# AT91.net
KiCad netlist of a schematic drawn in Altium Designer
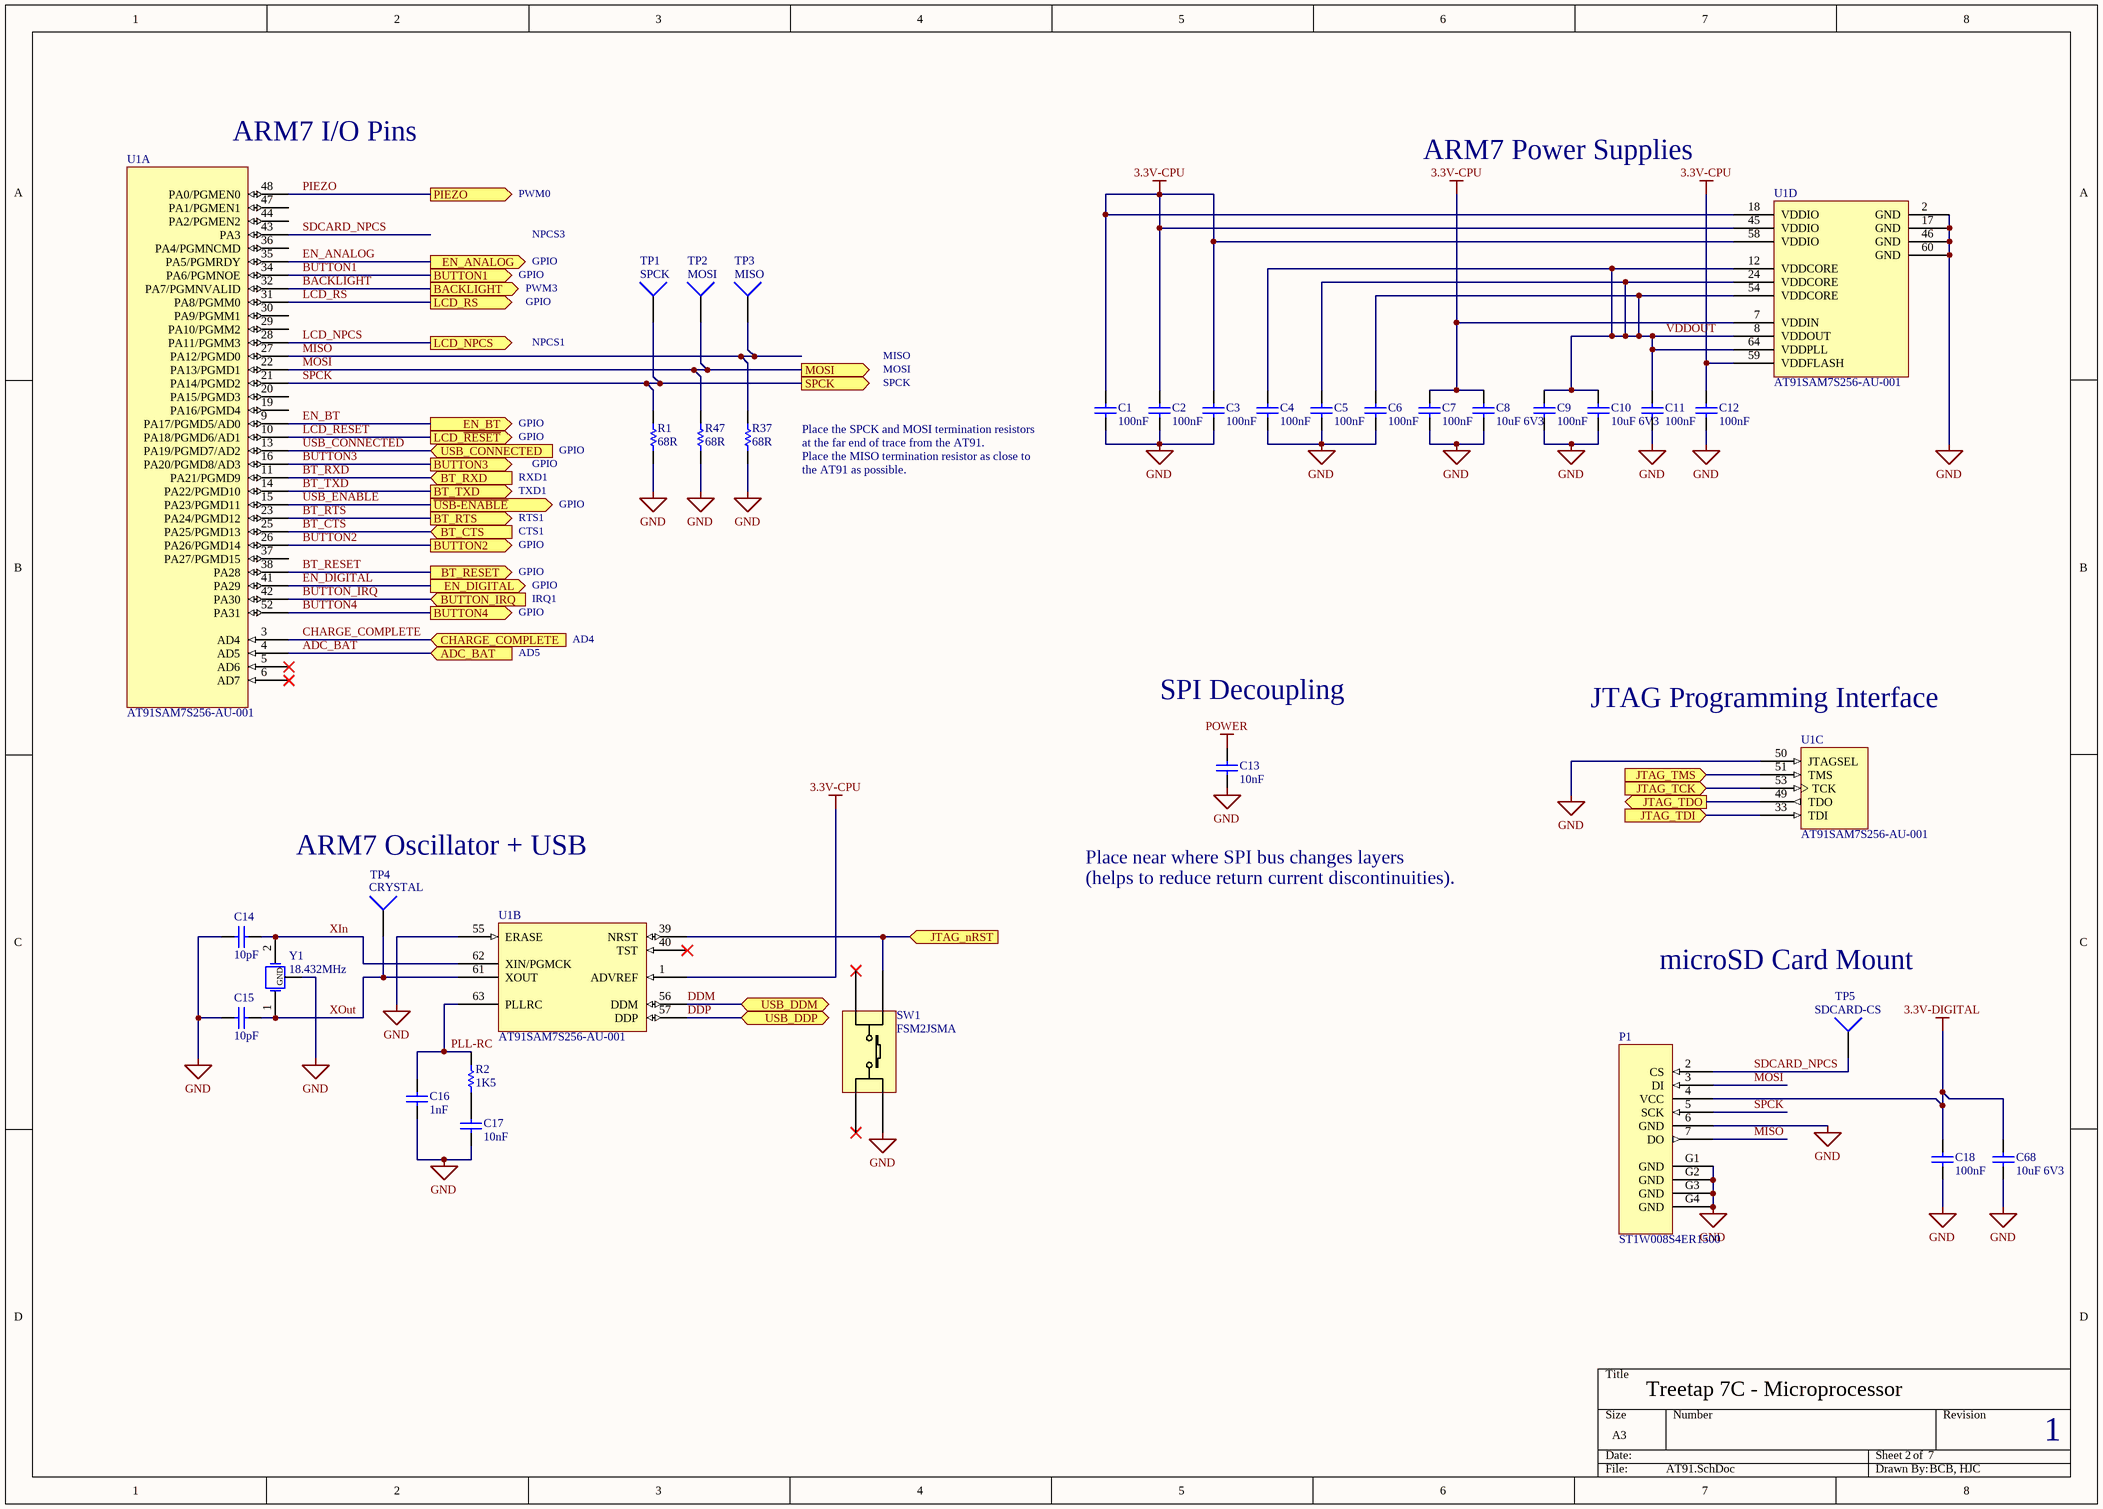
[diagram p0: AT91.SchDoc]

(export (version "E")
  (design (tool "Eeschema 10.0.6"))
  (components
    (comp (ref "C1")
      (value "100nF")
      (footprint "CC0603")
      (description "0603 Capacitor")
      (fields (field (name "PART NUMBER") "100nF_CC0603"))
      (libsource (lib "ECE_Component_Library_2") (part "100nF_CC0603"))
    )
    (comp (ref "C2")
      (value "100nF")
      (footprint "CC0603")
      (description "0603 Capacitor")
      (fields (field (name "PART NUMBER") "100nF_CC0603"))
      (libsource (lib "ECE_Component_Library_2") (part "100nF_CC0603"))
    )
    (comp (ref "C3")
      (value "100nF")
      (footprint "CC0603")
      (description "0603 Capacitor")
      (fields (field (name "PART NUMBER") "100nF_CC0603"))
      (libsource (lib "ECE_Component_Library_2") (part "100nF_CC0603"))
    )
    (comp (ref "C4")
      (value "100nF")
      (footprint "CC0603")
      (description "0603 Capacitor")
      (fields (field (name "PART NUMBER") "100nF_CC0603"))
      (libsource (lib "ECE_Component_Library_2") (part "100nF_CC0603"))
    )
    (comp (ref "C5")
      (value "100nF")
      (footprint "CC0603")
      (description "0603 Capacitor")
      (fields (field (name "PART NUMBER") "100nF_CC0603"))
      (libsource (lib "ECE_Component_Library_2") (part "100nF_CC0603"))
    )
    (comp (ref "C6")
      (value "100nF")
      (footprint "CC0603")
      (description "0603 Capacitor")
      (fields (field (name "PART NUMBER") "100nF_CC0603"))
      (libsource (lib "ECE_Component_Library_2") (part "100nF_CC0603"))
    )
    (comp (ref "C7")
      (value "100nF")
      (footprint "CC0603")
      (description "0603 Capacitor")
      (fields (field (name "PART NUMBER") "100nF_CC0603"))
      (libsource (lib "ECE_Component_Library_2") (part "100nF_CC0603"))
    )
    (comp (ref "C8")
      (value "10uF 6V3")
      (footprint "CC0603")
      (description "10uF 6.3V 0603 ceramic capacitor")
      (fields (field (name "MANUFACTURER") "Multicomp") (field (name "PART NUMBER") "MCCA000517"))
      (libsource (lib "TreetapParts") (part "10uF_CC0603_6V3"))
    )
    (comp (ref "C9")
      (value "100nF")
      (footprint "CC0603")
      (description "0603 Capacitor")
      (fields (field (name "PART NUMBER") "100nF_CC0603"))
      (libsource (lib "ECE_Component_Library_2") (part "100nF_CC0603"))
    )
    (comp (ref "C10")
      (value "10uF 6V3")
      (footprint "CC0603")
      (description "10uF 6.3V 0603 ceramic capacitor")
      (fields (field (name "MANUFACTURER") "Multicomp") (field (name "PART NUMBER") "MCCA000517"))
      (libsource (lib "TreetapParts") (part "10uF_CC0603_6V3"))
    )
    (comp (ref "C11")
      (value "100nF")
      (footprint "CC0603")
      (description "0603 Capacitor")
      (fields (field (name "PART NUMBER") "100nF_CC0603"))
      (libsource (lib "ECE_Component_Library_2") (part "100nF_CC0603"))
    )
    (comp (ref "C12")
      (value "100nF")
      (footprint "CC0603")
      (description "0603 Capacitor")
      (fields (field (name "PART NUMBER") "100nF_CC0603"))
      (libsource (lib "ECE_Component_Library_2") (part "100nF_CC0603"))
    )
    (comp (ref "C13")
      (value "10nF")
      (footprint "CC0603")
      (description "0603 Capacitor")
      (fields (field (name "PART NUMBER") "10nF_CC0603"))
      (libsource (lib "ECE_Component_Library_2") (part "10nF_CC0603"))
    )
    (comp (ref "C14")
      (value "10pF")
      (footprint "CC0603")
      (description "0603 Capacitor")
      (fields (field (name "PART NUMBER") "10pF_CC0603"))
      (libsource (lib "ECE_Component_Library_2") (part "10pF_CC0603"))
    )
    (comp (ref "C15")
      (value "10pF")
      (footprint "CC0603")
      (description "0603 Capacitor")
      (fields (field (name "PART NUMBER") "10pF_CC0603"))
      (libsource (lib "ECE_Component_Library_2") (part "10pF_CC0603"))
    )
    (comp (ref "C16")
      (value "1nF")
      (footprint "CC0603")
      (description "0603 Capacitor")
      (fields (field (name "PART NUMBER") "1nF_CC0603"))
      (libsource (lib "ECE_Component_Library_2") (part "1nF_CC0603"))
    )
    (comp (ref "C17")
      (value "10nF")
      (footprint "CC0603")
      (description "0603 Capacitor")
      (fields (field (name "PART NUMBER") "10nF_CC0603"))
      (libsource (lib "ECE_Component_Library_2") (part "10nF_CC0603"))
    )
    (comp (ref "C18")
      (value "100nF")
      (footprint "CC0603")
      (description "0603 Capacitor")
      (fields (field (name "PART NUMBER") "100nF_CC0603"))
      (libsource (lib "ECE_Component_Library_2") (part "100nF_CC0603"))
    )
    (comp (ref "C68")
      (value "10uF 6V3")
      (footprint "CC0603")
      (description "10uF 6.3V 0603 ceramic capacitor")
      (fields (field (name "MANUFACTURER") "Multicomp") (field (name "PART NUMBER") "MCCA000517"))
      (libsource (lib "TreetapParts") (part "10uF_CC0603_6V3"))
    )
    (comp (ref "P1")
      (value "ST1W008S4ER1500")
      (footprint "ST1W008S4ER1500")
      (description "microSD mount")
      (fields (field (name "MANUFACTURER") "JAE"))
      (libsource (lib "TreetapParts") (part "ST1W008S4ER1500"))
    )
    (comp (ref "R1")
      (value "68R")
      (footprint "R0603")
      (description "0603 Resistor")
      (fields (field (name "PART NUMBER") "68R_R0603"))
      (libsource (lib "ECE_Component_Library_2") (part "68R_R0603"))
    )
    (comp (ref "R2")
      (value "1K5")
      (footprint "R0603")
      (description "0603 Resistor")
      (fields (field (name "PART NUMBER") "1K5_R0603"))
      (libsource (lib "ECE_Component_Library_2") (part "1K5_R0603"))
    )
    (comp (ref "R37")
      (value "68R")
      (footprint "R0603")
      (description "0603 Resistor")
      (fields (field (name "PART NUMBER") "68R_R0603"))
      (libsource (lib "ECE_Component_Library_2") (part "68R_R0603"))
    )
    (comp (ref "R47")
      (value "68R")
      (footprint "R0603")
      (description "0603 Resistor")
      (fields (field (name "PART NUMBER") "68R_R0603"))
      (libsource (lib "ECE_Component_Library_2") (part "68R_R0603"))
    )
    (comp (ref "SW1")
      (value "FSM2JSMA")
      (footprint "FSM2JSMA")
      (description "DPST SMD Switch")
      (fields (field (name "MANUFACTURER") "Tyco Electronics"))
      (libsource (lib "TreetapParts") (part "FSM2JSMA"))
    )
    (comp (ref "TP1")
      (value "SPCK")
      (footprint "SMTP_1")
      (description "Test point hook (surface mount)")
      (fields (field (name "MANUFACTURER") "Harwin") (field (name "PART NUMBER") "S1751-46"))
      (libsource (lib "TreetapParts") (part "SMTestPoint"))
    )
    (comp (ref "TP2")
      (value "MOSI")
      (footprint "SMTP_1")
      (description "Test point hook (surface mount)")
      (fields (field (name "MANUFACTURER") "Harwin") (field (name "PART NUMBER") "S1751-46"))
      (libsource (lib "TreetapParts") (part "SMTestPoint"))
    )
    (comp (ref "TP3")
      (value "MISO")
      (footprint "SMTP_1")
      (description "Test point hook (surface mount)")
      (fields (field (name "MANUFACTURER") "Harwin") (field (name "PART NUMBER") "S1751-46"))
      (libsource (lib "TreetapParts") (part "SMTestPoint"))
    )
    (comp (ref "TP4")
      (value "CRYSTAL")
      (footprint "SMTP_1")
      (description "Test point hook (surface mount)")
      (fields (field (name "MANUFACTURER") "Harwin") (field (name "PART NUMBER") "S1751-46"))
      (libsource (lib "TreetapParts") (part "SMTestPoint"))
    )
    (comp (ref "TP5")
      (value "SDCARD-CS")
      (footprint "SMTP_1")
      (description "Test point hook (surface mount)")
      (fields (field (name "MANUFACTURER") "Harwin") (field (name "PART NUMBER") "S1751-46"))
      (libsource (lib "TreetapParts") (part "SMTestPoint"))
    )
    (comp (ref "U1")
      (value "AT91SAM7S256-AU-001")
      (footprint "LQFP64_L")
      (fields (field (name "MANUFACTURER") "Atmel") (field (name "PART NUMBER") "AT91SAM7S256"))
      (libsource (lib "") (part "AT91SAM7S256-AU-001_1"))
    )
    (comp (ref "Y1")
      (value "18.432MHz")
      (footprint "ABM10-18.432MHZ-E20-T")
      (description "18.432MHz SMT crystal 2x2.5mm 20ppm")
      (fields
        (field (name "PART NUMBER") "ABM10-18.432MHZ-E20-T")
        (field (name "MANUFACTURER") "Abracon Corporation")
      )
      (libsource (lib "TreetapParts") (part "ABM10-18.432MHZ-E20-T"))
    )
  )
  (nets
    (net (code "1") (name "/ADC_BAT") (class "Default")
      (node (ref "U1") (pin "4") (pinfunction "AD5_4") (pintype "input"))
    )
    (net (code "2") (name "/BACKLIGHT") (class "Default")
      (node (ref "U1") (pin "32") (pinfunction "PA7/PGMNVALID_32") (pintype "bidirectional"))
    )
    (net (code "3") (name "/BT_CTS") (class "Default")
      (node (ref "U1") (pin "25") (pinfunction "PA25/PGMD13_25") (pintype "bidirectional"))
    )
    (net (code "4") (name "/BT_RESET") (class "Default")
      (node (ref "U1") (pin "38") (pinfunction "PA28_38") (pintype "bidirectional"))
    )
    (net (code "5") (name "/BT_RTS") (class "Default")
      (node (ref "U1") (pin "23") (pinfunction "PA24/PGMD12_23") (pintype "bidirectional"))
    )
    (net (code "6") (name "/BT_RXD") (class "Default")
      (node (ref "U1") (pin "11") (pinfunction "PA21/PGMD9_11") (pintype "bidirectional"))
    )
    (net (code "7") (name "/BT_TXD") (class "Default")
      (node (ref "U1") (pin "14") (pinfunction "PA22/PGMD10_14") (pintype "bidirectional"))
    )
    (net (code "8") (name "/BUTTON1") (class "Default")
      (node (ref "U1") (pin "34") (pinfunction "PA6/PGMNOE_34") (pintype "bidirectional"))
    )
    (net (code "9") (name "/BUTTON2") (class "Default")
      (node (ref "U1") (pin "26") (pinfunction "PA26/PGMD14_26") (pintype "bidirectional"))
    )
    (net (code "10") (name "/BUTTON3") (class "Default")
      (node (ref "U1") (pin "16") (pinfunction "PA20/PGMD8/AD3_16") (pintype "bidirectional"))
    )
    (net (code "11") (name "/BUTTON4") (class "Default")
      (node (ref "U1") (pin "52") (pinfunction "PA31_52") (pintype "bidirectional"))
    )
    (net (code "12") (name "/BUTTON_IRQ") (class "Default")
      (node (ref "U1") (pin "42") (pinfunction "PA30_42") (pintype "bidirectional"))
    )
    (net (code "13") (name "/CHARGE_COMPLETE") (class "Default")
      (node (ref "U1") (pin "3") (pinfunction "AD4_3") (pintype "input"))
    )
    (net (code "14") (name "/DDM") (class "Default")
      (node (ref "U1") (pin "56") (pinfunction "DDM_56") (pintype "bidirectional"))
    )
    (net (code "15") (name "/DDP") (class "Default")
      (node (ref "U1") (pin "57") (pinfunction "DDP_57") (pintype "bidirectional"))
    )
    (net (code "16") (name "/EN_ANALOG") (class "Default")
      (node (ref "U1") (pin "35") (pinfunction "PA5/PGMRDY_35") (pintype "bidirectional"))
    )
    (net (code "17") (name "/EN_BT") (class "Default")
      (node (ref "U1") (pin "9") (pinfunction "PA17/PGMD5/AD0_9") (pintype "bidirectional"))
    )
    (net (code "18") (name "/EN_DIGITAL") (class "Default")
      (node (ref "U1") (pin "41") (pinfunction "PA29_41") (pintype "bidirectional"))
    )
    (net (code "19") (name "/JTAG_TCK") (class "Default")
      (node (ref "U1") (pin "53") (pinfunction "TCK_53") (pintype "input"))
    )
    (net (code "20") (name "/JTAG_TDI") (class "Default")
      (node (ref "U1") (pin "33") (pinfunction "TDI_33") (pintype "input"))
    )
    (net (code "21") (name "/JTAG_TDO") (class "Default")
      (node (ref "U1") (pin "49") (pinfunction "TDO_49") (pintype "output"))
    )
    (net (code "22") (name "/JTAG_TMS") (class "Default")
      (node (ref "U1") (pin "51") (pinfunction "TMS_51") (pintype "input"))
    )
    (net (code "23") (name "/JTAG_nRST") (class "Default")
      (node (ref "SW1") (pin "1") (pinfunction "1_1") (pintype "passive"))
      (node (ref "U1") (pin "39") (pinfunction "NRST_39") (pintype "bidirectional"))
    )
    (net (code "24") (name "/LCD_NPCS") (class "Default")
      (node (ref "U1") (pin "28") (pinfunction "PA11/PGMM3_28") (pintype "bidirectional"))
    )
    (net (code "25") (name "/LCD_RESET") (class "Default")
      (node (ref "U1") (pin "10") (pinfunction "PA18/PGMD6/AD1_10") (pintype "bidirectional"))
    )
    (net (code "26") (name "/LCD_RS") (class "Default")
      (node (ref "U1") (pin "31") (pinfunction "PA8/PGMM0_31") (pintype "bidirectional"))
    )
    (net (code "27") (name "/MISO") (class "Default")
      (node (ref "P1") (pin "7") (pinfunction "DO_7") (pintype "output"))
      (node (ref "R37") (pin "2") (pinfunction "2_2") (pintype "passive"))
      (node (ref "TP3") (pin "1") (pinfunction "1_1") (pintype "passive"))
      (node (ref "U1") (pin "27") (pinfunction "PA12/PGMD0_27") (pintype "bidirectional"))
    )
    (net (code "28") (name "/MOSI") (class "Default")
      (node (ref "P1") (pin "3") (pinfunction "DI_3") (pintype "input"))
      (node (ref "R47") (pin "2") (pinfunction "2_2") (pintype "passive"))
      (node (ref "TP2") (pin "1") (pinfunction "1_1") (pintype "passive"))
      (node (ref "U1") (pin "22") (pinfunction "PA13/PGMD1_22") (pintype "bidirectional"))
    )
    (net (code "29") (name "/PIEZO") (class "Default")
      (node (ref "U1") (pin "48") (pinfunction "PA0/PGMEN0_48") (pintype "bidirectional"))
    )
    (net (code "30") (name "/PLL-RC") (class "Default")
      (node (ref "C16") (pin "2") (pinfunction "2_2") (pintype "passive"))
      (node (ref "R2") (pin "2") (pinfunction "2_2") (pintype "passive"))
      (node (ref "U1") (pin "63") (pinfunction "PLLRC_63") (pintype "passive"))
    )
    (net (code "31") (name "/SDCARD_NPCS") (class "Default")
      (node (ref "P1") (pin "2") (pinfunction "CS_2") (pintype "input"))
      (node (ref "TP5") (pin "1") (pinfunction "1_1") (pintype "passive"))
      (node (ref "U1") (pin "43") (pinfunction "PA3_43") (pintype "bidirectional"))
    )
    (net (code "32") (name "/SPCK") (class "Default")
      (node (ref "P1") (pin "5") (pinfunction "SCK_5") (pintype "input"))
      (node (ref "R1") (pin "2") (pinfunction "2_2") (pintype "passive"))
      (node (ref "TP1") (pin "1") (pinfunction "1_1") (pintype "passive"))
      (node (ref "U1") (pin "21") (pinfunction "PA14/PGMD2_21") (pintype "bidirectional"))
    )
    (net (code "33") (name "/USB_CONNECTED") (class "Default")
      (node (ref "U1") (pin "13") (pinfunction "PA19/PGMD7/AD2_13") (pintype "bidirectional"))
    )
    (net (code "34") (name "/USB_ENABLE") (class "Default")
      (node (ref "U1") (pin "15") (pinfunction "PA23/PGMD11_15") (pintype "bidirectional"))
    )
    (net (code "35") (name "/VDDOUT") (class "Default")
      (node (ref "C10") (pin "2") (pinfunction "2_2") (pintype "passive"))
      (node (ref "C11") (pin "2") (pinfunction "2_2") (pintype "passive"))
      (node (ref "C4") (pin "2") (pinfunction "2_2") (pintype "passive"))
      (node (ref "C5") (pin "2") (pinfunction "2_2") (pintype "passive"))
      (node (ref "C6") (pin "2") (pinfunction "2_2") (pintype "passive"))
      (node (ref "C9") (pin "1") (pinfunction "1_1") (pintype "passive"))
      (node (ref "U1") (pin "12") (pinfunction "VDDCORE_12") (pintype "power_in"))
      (node (ref "U1") (pin "24") (pinfunction "VDDCORE_24") (pintype "power_in"))
      (node (ref "U1") (pin "54") (pinfunction "VDDCORE_54") (pintype "power_in"))
      (node (ref "U1") (pin "64") (pinfunction "VDDPLL_64") (pintype "power_in"))
      (node (ref "U1") (pin "8") (pinfunction "VDDOUT_8") (pintype "power_in"))
    )
    (net (code "36") (name "/XIn") (class "Default")
      (node (ref "C14") (pin "1") (pinfunction "1_1") (pintype "passive"))
      (node (ref "U1") (pin "62") (pinfunction "XIN/PGMCK_62") (pintype "passive"))
      (node (ref "Y1") (pin "2") (pinfunction "OSC2_2") (pintype "passive"))
    )
    (net (code "37") (name "/XOut") (class "Default")
      (node (ref "C15") (pin "2") (pinfunction "2_2") (pintype "passive"))
      (node (ref "TP4") (pin "1") (pinfunction "1_1") (pintype "passive"))
      (node (ref "U1") (pin "61") (pinfunction "XOUT_61") (pintype "passive"))
      (node (ref "Y1") (pin "1") (pinfunction "OSC1_1") (pintype "passive"))
    )
    (net (code "38") (name "3.3V-CPU") (class "Default")
      (node (ref "C1") (pin "2") (pinfunction "2_2") (pintype "passive"))
      (node (ref "C12") (pin "2") (pinfunction "2_2") (pintype "passive"))
      (node (ref "C2") (pin "2") (pinfunction "2_2") (pintype "passive"))
      (node (ref "C3") (pin "1") (pinfunction "1_1") (pintype "passive"))
      (node (ref "C7") (pin "1") (pinfunction "1_1") (pintype "passive"))
      (node (ref "C8") (pin "2") (pinfunction "2_2") (pintype "passive"))
      (node (ref "U1") (pin "1") (pinfunction "ADVREF_1") (pintype "input"))
      (node (ref "U1") (pin "18") (pinfunction "VDDIO_18") (pintype "power_in"))
      (node (ref "U1") (pin "45") (pinfunction "VDDIO_45") (pintype "power_in"))
      (node (ref "U1") (pin "58") (pinfunction "VDDIO_58") (pintype "power_in"))
      (node (ref "U1") (pin "59") (pinfunction "VDDFLASH_59") (pintype "power_in"))
      (node (ref "U1") (pin "7") (pinfunction "VDDIN_7") (pintype "power_in"))
    )
    (net (code "39") (name "3.3V-DIGITAL") (class "Default")
      (node (ref "C18") (pin "2") (pinfunction "2_2") (pintype "passive"))
      (node (ref "C68") (pin "2") (pinfunction "2_2") (pintype "passive"))
      (node (ref "P1") (pin "4") (pinfunction "VCC_4") (pintype "power_in"))
    )
    (net (code "40") (name "GND") (class "Default")
      (node (ref "C1") (pin "1") (pinfunction "1_1") (pintype "passive"))
      (node (ref "C10") (pin "1") (pinfunction "1_1") (pintype "passive"))
      (node (ref "C11") (pin "1") (pinfunction "1_1") (pintype "passive"))
      (node (ref "C12") (pin "1") (pinfunction "1_1") (pintype "passive"))
      (node (ref "C13") (pin "1") (pinfunction "1_1") (pintype "passive"))
      (node (ref "C14") (pin "2") (pinfunction "2_2") (pintype "passive"))
      (node (ref "C15") (pin "1") (pinfunction "1_1") (pintype "passive"))
      (node (ref "C16") (pin "1") (pinfunction "1_1") (pintype "passive"))
      (node (ref "C17") (pin "1") (pinfunction "1_1") (pintype "passive"))
      (node (ref "C18") (pin "1") (pinfunction "1_1") (pintype "passive"))
      (node (ref "C2") (pin "1") (pinfunction "1_1") (pintype "passive"))
      (node (ref "C3") (pin "2") (pinfunction "2_2") (pintype "passive"))
      (node (ref "C4") (pin "1") (pinfunction "1_1") (pintype "passive"))
      (node (ref "C5") (pin "1") (pinfunction "1_1") (pintype "passive"))
      (node (ref "C6") (pin "1") (pinfunction "1_1") (pintype "passive"))
      (node (ref "C68") (pin "1") (pinfunction "1_1") (pintype "passive"))
      (node (ref "C7") (pin "2") (pinfunction "2_2") (pintype "passive"))
      (node (ref "C8") (pin "1") (pinfunction "1_1") (pintype "passive"))
      (node (ref "C9") (pin "2") (pinfunction "2_2") (pintype "passive"))
      (node (ref "P1") (pin "6") (pinfunction "GND_6") (pintype "power_in"))
      (node (ref "P1") (pin "G1") (pinfunction "GND_G1") (pintype "power_in"))
      (node (ref "P1") (pin "G2") (pinfunction "GND_G2") (pintype "power_in"))
      (node (ref "P1") (pin "G3") (pinfunction "GND_G3") (pintype "power_in"))
      (node (ref "P1") (pin "G4") (pinfunction "GND_G4") (pintype "power_in"))
      (node (ref "R1") (pin "1") (pinfunction "1_1") (pintype "passive"))
      (node (ref "R37") (pin "1") (pinfunction "1_1") (pintype "passive"))
      (node (ref "R47") (pin "1") (pinfunction "1_1") (pintype "passive"))
      (node (ref "SW1") (pin "4") (pinfunction "4_4") (pintype "passive"))
      (node (ref "U1") (pin "17") (pinfunction "GND_17") (pintype "power_in"))
      (node (ref "U1") (pin "2") (pinfunction "GND_2") (pintype "power_in"))
      (node (ref "U1") (pin "46") (pinfunction "GND_46") (pintype "power_in"))
      (node (ref "U1") (pin "50") (pinfunction "JTAGSEL_50") (pintype "input"))
      (node (ref "U1") (pin "55") (pinfunction "ERASE_55") (pintype "input"))
      (node (ref "U1") (pin "60") (pinfunction "GND_60") (pintype "power_in"))
      (node (ref "Y1") (pin "G") (pinfunction "GND_G") (pintype "passive"))
    )
    (net (code "41") (name "Net-(C17-Pad2)") (class "Default")
      (node (ref "C17") (pin "2") (pinfunction "2_2") (pintype "passive"))
      (node (ref "R2") (pin "1") (pinfunction "1_1") (pintype "passive"))
    )
    (net (code "42") (name "POWER") (class "Default")
      (node (ref "C13") (pin "2") (pinfunction "2_2") (pintype "passive"))
    )
    (net (code "43") (name "unconnected-(SW1-Pad2)") (class "Default")
      (node (ref "SW1") (pin "2") (pinfunction "2_2") (pintype "passive+no_connect"))
    )
    (net (code "44") (name "unconnected-(SW1-Pad3)") (class "Default")
      (node (ref "SW1") (pin "3") (pinfunction "3_3") (pintype "passive+no_connect"))
    )
    (net (code "45") (name "unconnected-(U1A-AD6-Pad5)") (class "Default")
      (node (ref "U1") (pin "5") (pinfunction "AD6_5") (pintype "input+no_connect"))
    )
    (net (code "46") (name "unconnected-(U1A-AD7-Pad6)") (class "Default")
      (node (ref "U1") (pin "6") (pinfunction "AD7_6") (pintype "input+no_connect"))
    )
    (net (code "47") (name "unconnected-(U1A-PA1{slash}PGMEN1-Pad47)") (class "Default")
      (node (ref "U1") (pin "47") (pinfunction "PA1/PGMEN1_47") (pintype "bidirectional"))
    )
    (net (code "48") (name "unconnected-(U1A-PA2{slash}PGMEN2-Pad44)") (class "Default")
      (node (ref "U1") (pin "44") (pinfunction "PA2/PGMEN2_44") (pintype "bidirectional"))
    )
    (net (code "49") (name "unconnected-(U1A-PA4{slash}PGMNCMD-Pad36)") (class "Default")
      (node (ref "U1") (pin "36") (pinfunction "PA4/PGMNCMD_36") (pintype "bidirectional"))
    )
    (net (code "50") (name "unconnected-(U1A-PA9{slash}PGMM1-Pad30)") (class "Default")
      (node (ref "U1") (pin "30") (pinfunction "PA9/PGMM1_30") (pintype "bidirectional"))
    )
    (net (code "51") (name "unconnected-(U1A-PA10{slash}PGMM2-Pad29)") (class "Default")
      (node (ref "U1") (pin "29") (pinfunction "PA10/PGMM2_29") (pintype "bidirectional"))
    )
    (net (code "52") (name "unconnected-(U1A-PA15{slash}PGMD3-Pad20)") (class "Default")
      (node (ref "U1") (pin "20") (pinfunction "PA15/PGMD3_20") (pintype "bidirectional"))
    )
    (net (code "53") (name "unconnected-(U1A-PA16{slash}PGMD4-Pad19)") (class "Default")
      (node (ref "U1") (pin "19") (pinfunction "PA16/PGMD4_19") (pintype "bidirectional"))
    )
    (net (code "54") (name "unconnected-(U1A-PA27{slash}PGMD15-Pad37)") (class "Default")
      (node (ref "U1") (pin "37") (pinfunction "PA27/PGMD15_37") (pintype "bidirectional"))
    )
    (net (code "55") (name "unconnected-(U1B-TST-Pad40)") (class "Default")
      (node (ref "U1") (pin "40") (pinfunction "TST_40") (pintype "input+no_connect"))
    )
  )
)
